# Front_panel_piezo.net
KiCad netlist of a schematic drawn in EAGLE
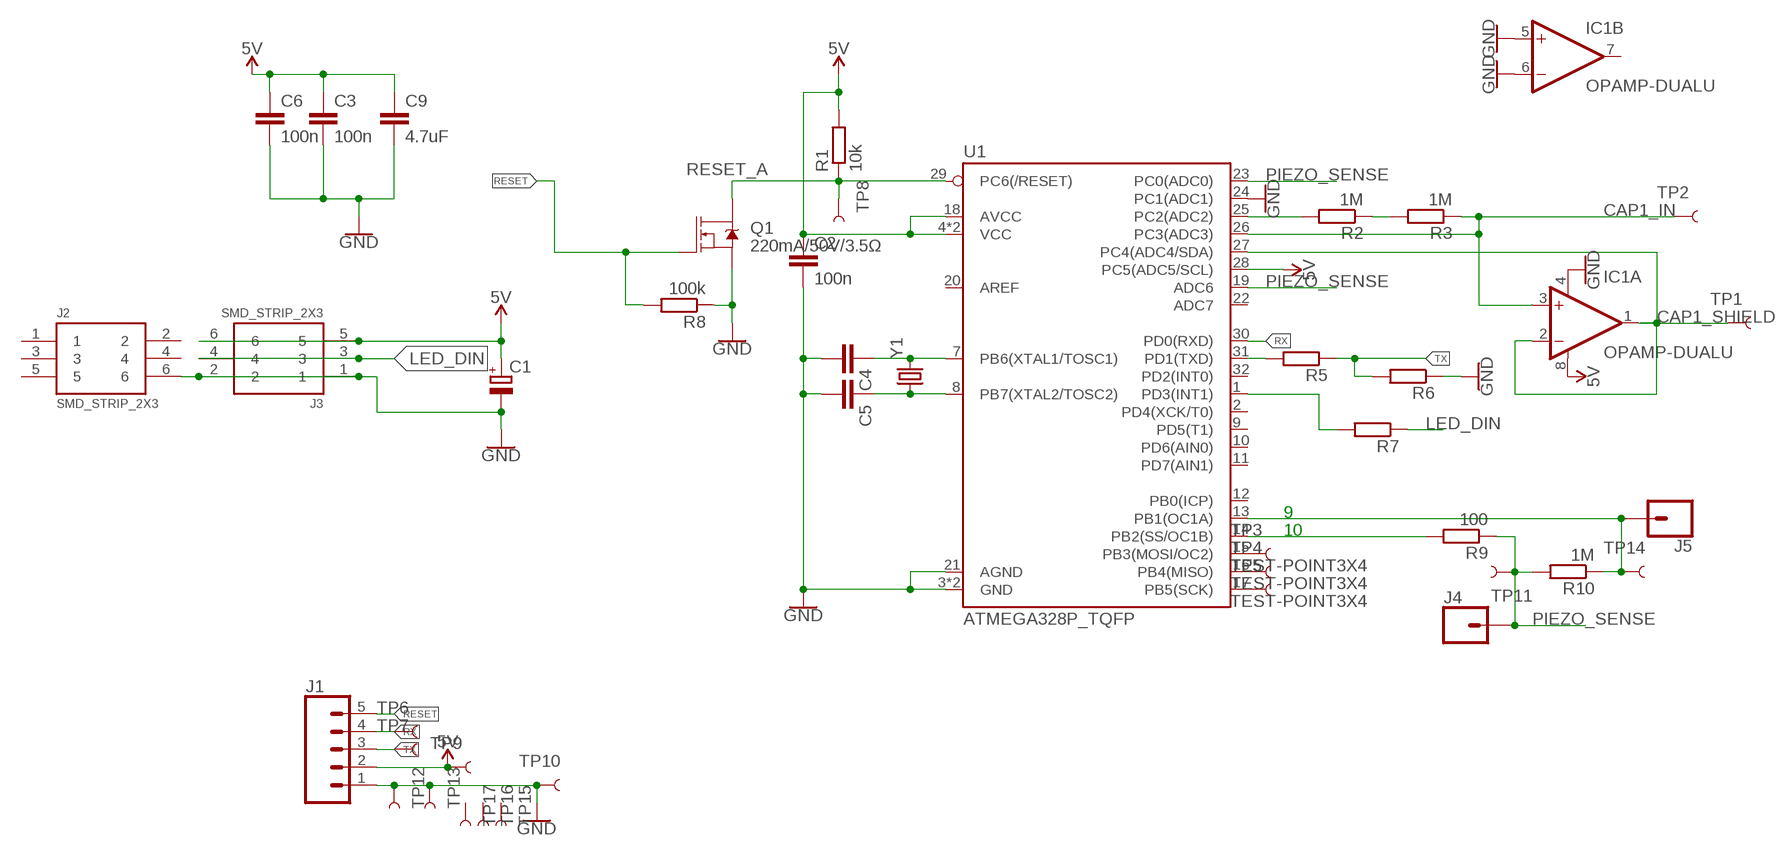
[diagram p0: schematic, sheet 1]

(export (version "E")
  (design (tool "Eeschema 10.0.6"))
  (components
    (comp (ref "C1")
      (value "CPOL-EUCT6032")
      (footprint "eagle-import:CT6032")
      (libsource (lib "eagle-import") (part "CPOL-EUCT6032"))
    )
    (comp (ref "C2")
      (value "100n")
      (footprint "eagle-import:C0805")
      (libsource (lib "eagle-import") (part "C-EUC0805"))
    )
    (comp (ref "C3")
      (value "100n")
      (footprint "eagle-import:C0805")
      (libsource (lib "eagle-import") (part "C-EUC0805"))
    )
    (comp (ref "C4")
      (value "C-EUC0805")
      (footprint "eagle-import:C0805")
      (libsource (lib "eagle-import") (part "C-EUC0805"))
    )
    (comp (ref "C5")
      (value "C-EUC0805")
      (footprint "eagle-import:C0805")
      (libsource (lib "eagle-import") (part "C-EUC0805"))
    )
    (comp (ref "C6")
      (value "100n")
      (footprint "eagle-import:C0805")
      (libsource (lib "eagle-import") (part "C-EUC0805"))
    )
    (comp (ref "C9")
      (value "4.7uF")
      (footprint "eagle-import:C0805")
      (libsource (lib "eagle-import") (part "C-EUC0805"))
    )
    (comp (ref "IC1")
      (value "OPAMP-DUALU")
      (footprint "eagle-import:SO08")
      (libsource (lib "eagle-import") (part "OPAMP-DUALU"))
    )
    (comp (ref "J1")
      (value "CONN_05SMD2")
      (footprint "eagle-import:1X05_1MM_RA")
      (libsource (lib "eagle-import") (part "CONN_05SMD2"))
    )
    (comp (ref "J2")
      (value "SMD_STRIP_2X3")
      (footprint "eagle-import:SMD_STRIP_2X3")
      (libsource (lib "eagle-import") (part "SMD_STRIP_2X3"))
    )
    (comp (ref "J3")
      (value "SMD_STRIP_2X3")
      (footprint "eagle-import:SMD_STRIP_2X3")
      (libsource (lib "eagle-import") (part "SMD_STRIP_2X3"))
    )
    (comp (ref "J4")
      (value "CONN_01SPRING-CONN")
      (footprint "eagle-import:SPRING-CONNECTOR")
      (libsource (lib "eagle-import") (part "CONN_01SPRING-CONN"))
    )
    (comp (ref "J5")
      (value "CONN_01SPRING-CONN")
      (footprint "eagle-import:SPRING-CONNECTOR")
      (libsource (lib "eagle-import") (part "CONN_01SPRING-CONN"))
    )
    (comp (ref "Q1")
      (value "220mA/50V/3.5Ω")
      (footprint "eagle-import:SOT23-3")
      (libsource (lib "eagle-import") (part "MOSFET-NCH-BSS138"))
    )
    (comp (ref "R1")
      (value "10k")
      (footprint "eagle-import:R0805")
      (libsource (lib "eagle-import") (part "R-EU_R0805"))
    )
    (comp (ref "R2")
      (value "1M")
      (footprint "eagle-import:R0805")
      (libsource (lib "eagle-import") (part "R-EU_R0805"))
    )
    (comp (ref "R3")
      (value "1M")
      (footprint "eagle-import:R0805")
      (libsource (lib "eagle-import") (part "R-EU_R0805"))
    )
    (comp (ref "R5")
      (value "R-EU_R0805")
      (footprint "eagle-import:R0805")
      (libsource (lib "eagle-import") (part "R-EU_R0805"))
    )
    (comp (ref "R6")
      (value "R-EU_R0805")
      (footprint "eagle-import:R0805")
      (libsource (lib "eagle-import") (part "R-EU_R0805"))
    )
    (comp (ref "R7")
      (value "R-EU_R0805")
      (footprint "eagle-import:R0805")
      (libsource (lib "eagle-import") (part "R-EU_R0805"))
    )
    (comp (ref "R8")
      (value "100k")
      (footprint "eagle-import:R0805")
      (libsource (lib "eagle-import") (part "R-EU_R0805"))
    )
    (comp (ref "R9")
      (value "100")
      (footprint "eagle-import:R0805")
      (libsource (lib "eagle-import") (part "R-EU_R0805"))
    )
    (comp (ref "R10")
      (value "1M")
      (footprint "eagle-import:R0805")
      (libsource (lib "eagle-import") (part "R-EU_R0805"))
    )
    (comp (ref "TP1")
      (value "TEST-POINT3X4")
      (footprint "eagle-import:PAD.03X.04")
      (libsource (lib "eagle-import") (part "TEST-POINT3X4"))
    )
    (comp (ref "TP2")
      (value "TEST-POINT3X4")
      (footprint "eagle-import:PAD.03X.04")
      (libsource (lib "eagle-import") (part "TEST-POINT3X4"))
    )
    (comp (ref "TP3")
      (value "TEST-POINT3X4")
      (footprint "eagle-import:PAD.03X.04")
      (libsource (lib "eagle-import") (part "TEST-POINT3X4"))
    )
    (comp (ref "TP4")
      (value "TEST-POINT3X4")
      (footprint "eagle-import:PAD.03X.04")
      (libsource (lib "eagle-import") (part "TEST-POINT3X4"))
    )
    (comp (ref "TP5")
      (value "TEST-POINT3X4")
      (footprint "eagle-import:PAD.03X.04")
      (libsource (lib "eagle-import") (part "TEST-POINT3X4"))
    )
    (comp (ref "TP6")
      (value "TEST-POINT3X4")
      (footprint "eagle-import:PAD.03X.04")
      (libsource (lib "eagle-import") (part "TEST-POINT3X4"))
    )
    (comp (ref "TP7")
      (value "TEST-POINT3X4")
      (footprint "eagle-import:PAD.03X.04")
      (libsource (lib "eagle-import") (part "TEST-POINT3X4"))
    )
    (comp (ref "TP8")
      (value "TEST-POINT3X4")
      (footprint "eagle-import:PAD.03X.04")
      (libsource (lib "eagle-import") (part "TEST-POINT3X4"))
    )
    (comp (ref "TP9")
      (value "TEST-POINT3X4")
      (footprint "eagle-import:PAD.03X.04")
      (libsource (lib "eagle-import") (part "TEST-POINT3X4"))
    )
    (comp (ref "TP10")
      (value "TEST-POINT3X4")
      (footprint "eagle-import:PAD.03X.04")
      (libsource (lib "eagle-import") (part "TEST-POINT3X4"))
    )
    (comp (ref "TP11")
      (value "TEST-POINT3X4")
      (footprint "eagle-import:PAD.03X.04")
      (libsource (lib "eagle-import") (part "TEST-POINT3X4"))
    )
    (comp (ref "TP12")
      (value "TEST-POINT3X4")
      (footprint "eagle-import:PAD.03X.04")
      (libsource (lib "eagle-import") (part "TEST-POINT3X4"))
    )
    (comp (ref "TP13")
      (value "TEST-POINT3X4")
      (footprint "eagle-import:PAD.03X.04")
      (libsource (lib "eagle-import") (part "TEST-POINT3X4"))
    )
    (comp (ref "TP14")
      (value "TEST-POINT3X4")
      (footprint "eagle-import:PAD.03X.04")
      (libsource (lib "eagle-import") (part "TEST-POINT3X4"))
    )
    (comp (ref "TP15")
      (value "TEST-POINT3X4")
      (footprint "eagle-import:PAD.03X.04")
      (libsource (lib "eagle-import") (part "TEST-POINT3X4"))
    )
    (comp (ref "TP16")
      (value "TEST-POINT3X4")
      (footprint "eagle-import:PAD.03X.04")
      (libsource (lib "eagle-import") (part "TEST-POINT3X4"))
    )
    (comp (ref "TP17")
      (value "TEST-POINT3X4")
      (footprint "eagle-import:PAD.03X.04")
      (libsource (lib "eagle-import") (part "TEST-POINT3X4"))
    )
    (comp (ref "U1")
      (value "ATMEGA328P_TQFP")
      (footprint "eagle-import:TQFP32-08")
      (libsource (lib "eagle-import") (part "ATMEGA328P_TQFP"))
    )
    (comp (ref "Y1")
      (value "CRYSTALSMD-3.2X2.5")
      (footprint "eagle-import:CRYSTAL-SMD-3.2X2.5MM")
      (libsource (lib "eagle-import") (part "CRYSTALSMD-3.2X2.5"))
    )
  )
  (nets
    (net (code "1") (name "/CAP1_IN") (class "Default")
      (node (ref "IC1") (pin "3") (pinfunction "+IN_3") (pintype "input"))
      (node (ref "R3") (pin "1") (pinfunction "1_1") (pintype "passive"))
      (node (ref "TP2") (pin "P$1") (pinfunction "1_P$1") (pintype "bidirectional"))
      (node (ref "U1") (pin "26") (pinfunction "PC3(ADC3)_26") (pintype "bidirectional"))
    )
    (net (code "2") (name "/CAP1_SHIELD") (class "Default")
      (node (ref "IC1") (pin "1") (pinfunction "OUT_1") (pintype "output"))
      (node (ref "IC1") (pin "2") (pinfunction "-IN_2") (pintype "input"))
      (node (ref "TP1") (pin "P$1") (pinfunction "1_P$1") (pintype "bidirectional"))
      (node (ref "U1") (pin "27") (pinfunction "PC4(ADC4/SDA)_27") (pintype "bidirectional"))
    )
    (net (code "3") (name "/PIEZO_SENSE") (class "Default")
      (node (ref "J4") (pin "P$2") (pinfunction "1_P$2") (pintype "passive"))
      (node (ref "R10") (pin "2") (pinfunction "2_2") (pintype "passive"))
      (node (ref "R9") (pin "1") (pinfunction "1_1") (pintype "passive"))
      (node (ref "TP11") (pin "P$1") (pinfunction "1_P$1") (pintype "bidirectional"))
      (node (ref "U1") (pin "19") (pinfunction "ADC6_19") (pintype "bidirectional"))
      (node (ref "U1") (pin "23") (pinfunction "PC0(ADC0)_23") (pintype "bidirectional"))
    )
    (net (code "4") (name "/RESET_A") (class "Default")
      (node (ref "Q1") (pin "3") (pinfunction "D_3") (pintype "bidirectional"))
      (node (ref "R1") (pin "1") (pinfunction "1_1") (pintype "passive"))
      (node (ref "TP8") (pin "P$1") (pinfunction "1_P$1") (pintype "bidirectional"))
      (node (ref "U1") (pin "29") (pinfunction "PC6(/RESET)_29") (pintype "bidirectional"))
    )
    (net (code "5") (name "5V") (class "Default")
      (node (ref "C1") (pin "-") (pinfunction "+_-") (pintype "passive"))
      (node (ref "C2") (pin "1") (pinfunction "1_1") (pintype "passive"))
      (node (ref "C3") (pin "1") (pinfunction "1_1") (pintype "passive"))
      (node (ref "C6") (pin "1") (pinfunction "1_1") (pintype "passive"))
      (node (ref "C9") (pin "1") (pinfunction "1_1") (pintype "passive"))
      (node (ref "IC1") (pin "8") (pinfunction "V+_8") (pintype "power_in"))
      (node (ref "J1") (pin "2") (pinfunction "2_2") (pintype "passive"))
      (node (ref "J3") (pin "5") (pinfunction "5_5") (pintype "bidirectional"))
      (node (ref "J3") (pin "6") (pinfunction "6_6") (pintype "bidirectional"))
      (node (ref "R1") (pin "2") (pinfunction "2_2") (pintype "passive"))
      (node (ref "TP9") (pin "P$1") (pinfunction "1_P$1") (pintype "bidirectional"))
      (node (ref "U1") (pin "18") (pinfunction "AVCC_18") (pintype "bidirectional"))
      (node (ref "U1") (pin "28") (pinfunction "PC5(ADC5/SCL)_28") (pintype "bidirectional"))
      (node (ref "U1") (pin "4") (pinfunction "VCC_4") (pintype "bidirectional"))
      (node (ref "U1") (pin "6") (pinfunction "VCC_6") (pintype "bidirectional"))
    )
    (net (code "6") (name "GND") (class "Default")
      (node (ref "C1") (pin "+") (pinfunction "-_+") (pintype "passive"))
      (node (ref "C2") (pin "2") (pinfunction "2_2") (pintype "passive"))
      (node (ref "C3") (pin "2") (pinfunction "2_2") (pintype "passive"))
      (node (ref "C4") (pin "2") (pinfunction "2_2") (pintype "passive"))
      (node (ref "C5") (pin "2") (pinfunction "2_2") (pintype "passive"))
      (node (ref "C6") (pin "2") (pinfunction "2_2") (pintype "passive"))
      (node (ref "C9") (pin "2") (pinfunction "2_2") (pintype "passive"))
      (node (ref "IC1") (pin "4") (pinfunction "V-_4") (pintype "power_in"))
      (node (ref "IC1") (pin "5") (pinfunction "+IN_5") (pintype "input"))
      (node (ref "IC1") (pin "6") (pinfunction "-IN_6") (pintype "input"))
      (node (ref "J1") (pin "1") (pinfunction "1_1") (pintype "passive"))
      (node (ref "J2") (pin "6") (pinfunction "6_6") (pintype "bidirectional"))
      (node (ref "J3") (pin "1") (pinfunction "1_1") (pintype "bidirectional"))
      (node (ref "J3") (pin "2") (pinfunction "2_2") (pintype "bidirectional"))
      (node (ref "Q1") (pin "2") (pinfunction "S_2") (pintype "bidirectional"))
      (node (ref "R6") (pin "1") (pinfunction "1_1") (pintype "passive"))
      (node (ref "R8") (pin "1") (pinfunction "1_1") (pintype "passive"))
      (node (ref "TP10") (pin "P$1") (pinfunction "1_P$1") (pintype "bidirectional"))
      (node (ref "TP12") (pin "P$1") (pinfunction "1_P$1") (pintype "bidirectional"))
      (node (ref "TP13") (pin "P$1") (pinfunction "1_P$1") (pintype "bidirectional"))
      (node (ref "U1") (pin "21") (pinfunction "AGND_21") (pintype "bidirectional"))
      (node (ref "U1") (pin "24") (pinfunction "PC1(ADC1)_24") (pintype "bidirectional"))
      (node (ref "U1") (pin "3") (pinfunction "GND_3") (pintype "bidirectional"))
      (node (ref "U1") (pin "5") (pinfunction "GND_5") (pintype "bidirectional"))
    )
    (net (code "7") (name "LED_DIN") (class "Default")
      (node (ref "J3") (pin "3") (pinfunction "3_3") (pintype "bidirectional"))
      (node (ref "J3") (pin "4") (pinfunction "4_4") (pintype "bidirectional"))
      (node (ref "R7") (pin "1") (pinfunction "1_1") (pintype "passive"))
    )
    (net (code "8") (name "Net-(J5-1)") (class "Default")
      (node (ref "J5") (pin "P$2") (pinfunction "1_P$2") (pintype "passive"))
      (node (ref "R10") (pin "1") (pinfunction "1_1") (pintype "passive"))
      (node (ref "TP14") (pin "P$1") (pinfunction "1_P$1") (pintype "bidirectional"))
      (node (ref "U1") (pin "13") (pinfunction "PB1(OC1A)_13") (pintype "bidirectional"))
    )
    (net (code "9") (name "Net-(R2-Pad1)") (class "Default")
      (node (ref "R2") (pin "1") (pinfunction "1_1") (pintype "passive"))
      (node (ref "R3") (pin "2") (pinfunction "2_2") (pintype "passive"))
    )
    (net (code "10") (name "Net-(TP3-1)") (class "Default")
      (node (ref "TP3") (pin "P$1") (pinfunction "1_P$1") (pintype "bidirectional"))
      (node (ref "U1") (pin "15") (pinfunction "PB3(MOSI/OC2)_15") (pintype "bidirectional"))
    )
    (net (code "11") (name "Net-(TP4-1)") (class "Default")
      (node (ref "TP4") (pin "P$1") (pinfunction "1_P$1") (pintype "bidirectional"))
      (node (ref "U1") (pin "16") (pinfunction "PB4(MISO)_16") (pintype "bidirectional"))
    )
    (net (code "12") (name "Net-(TP5-1)") (class "Default")
      (node (ref "TP5") (pin "P$1") (pinfunction "1_P$1") (pintype "bidirectional"))
      (node (ref "U1") (pin "17") (pinfunction "PB5(SCK)_17") (pintype "bidirectional"))
    )
    (net (code "13") (name "Net-(U1-PB2(SS{slash}OC1B))") (class "Default")
      (node (ref "R9") (pin "2") (pinfunction "2_2") (pintype "passive"))
      (node (ref "U1") (pin "14") (pinfunction "PB2(SS/OC1B)_14") (pintype "bidirectional"))
    )
    (net (code "14") (name "Net-(U1-PB6(XTAL1{slash}TOSC1))") (class "Default")
      (node (ref "C4") (pin "1") (pinfunction "1_1") (pintype "passive"))
      (node (ref "U1") (pin "7") (pinfunction "PB6(XTAL1/TOSC1)_7") (pintype "bidirectional"))
      (node (ref "Y1") (pin "3") (pinfunction "2_3") (pintype "passive"))
    )
    (net (code "15") (name "Net-(U1-PB7(XTAL2{slash}TOSC2))") (class "Default")
      (node (ref "C5") (pin "1") (pinfunction "1_1") (pintype "passive"))
      (node (ref "U1") (pin "8") (pinfunction "PB7(XTAL2/TOSC2)_8") (pintype "bidirectional"))
      (node (ref "Y1") (pin "1") (pinfunction "1_1") (pintype "passive"))
    )
    (net (code "16") (name "Net-(U1-PC2(ADC2))") (class "Default")
      (node (ref "R2") (pin "2") (pinfunction "2_2") (pintype "passive"))
      (node (ref "U1") (pin "25") (pinfunction "PC2(ADC2)_25") (pintype "bidirectional"))
    )
    (net (code "17") (name "Net-(U1-PD1(TXD))") (class "Default")
      (node (ref "R5") (pin "2") (pinfunction "2_2") (pintype "passive"))
      (node (ref "U1") (pin "31") (pinfunction "PD1(TXD)_31") (pintype "bidirectional"))
    )
    (net (code "18") (name "Net-(U1-PD3(INT1))") (class "Default")
      (node (ref "R7") (pin "2") (pinfunction "2_2") (pintype "passive"))
      (node (ref "U1") (pin "1") (pinfunction "PD3(INT1)_1") (pintype "bidirectional"))
    )
    (net (code "19") (name "RESET") (class "Default")
      (node (ref "J1") (pin "5") (pinfunction "5_5") (pintype "passive"))
      (node (ref "Q1") (pin "1") (pinfunction "G_1") (pintype "bidirectional"))
      (node (ref "R8") (pin "2") (pinfunction "2_2") (pintype "passive"))
    )
    (net (code "20") (name "RX") (class "Default")
      (node (ref "J1") (pin "4") (pinfunction "4_4") (pintype "passive"))
      (node (ref "TP6") (pin "P$1") (pinfunction "1_P$1") (pintype "bidirectional"))
      (node (ref "U1") (pin "30") (pinfunction "PD0(RXD)_30") (pintype "bidirectional"))
    )
    (net (code "21") (name "TX") (class "Default")
      (node (ref "J1") (pin "3") (pinfunction "3_3") (pintype "passive"))
      (node (ref "R5") (pin "1") (pinfunction "1_1") (pintype "passive"))
      (node (ref "R6") (pin "2") (pinfunction "2_2") (pintype "passive"))
      (node (ref "TP7") (pin "P$1") (pinfunction "1_P$1") (pintype "bidirectional"))
    )
    (net (code "22") (name "unconnected-(IC1B-OUT-Pad7)") (class "Default")
      (node (ref "IC1") (pin "7") (pinfunction "OUT_7") (pintype "output"))
    )
    (net (code "23") (name "unconnected-(J2-Pad1)") (class "Default")
      (node (ref "J2") (pin "1") (pinfunction "1_1") (pintype "bidirectional"))
    )
    (net (code "24") (name "unconnected-(J2-Pad2)") (class "Default")
      (node (ref "J2") (pin "2") (pinfunction "2_2") (pintype "bidirectional"))
    )
    (net (code "25") (name "unconnected-(J2-Pad3)") (class "Default")
      (node (ref "J2") (pin "3") (pinfunction "3_3") (pintype "bidirectional"))
    )
    (net (code "26") (name "unconnected-(J2-Pad4)") (class "Default")
      (node (ref "J2") (pin "4") (pinfunction "4_4") (pintype "bidirectional"))
    )
    (net (code "27") (name "unconnected-(J2-Pad5)") (class "Default")
      (node (ref "J2") (pin "5") (pinfunction "5_5") (pintype "bidirectional"))
    )
    (net (code "28") (name "unconnected-(TP15-1-PadP$1)") (class "Default")
      (node (ref "TP15") (pin "P$1") (pinfunction "1_P$1") (pintype "bidirectional"))
    )
    (net (code "29") (name "unconnected-(TP16-1-PadP$1)") (class "Default")
      (node (ref "TP16") (pin "P$1") (pinfunction "1_P$1") (pintype "bidirectional"))
    )
    (net (code "30") (name "unconnected-(TP17-1-PadP$1)") (class "Default")
      (node (ref "TP17") (pin "P$1") (pinfunction "1_P$1") (pintype "bidirectional"))
    )
    (net (code "31") (name "unconnected-(U1-ADC7-Pad22)") (class "Default")
      (node (ref "U1") (pin "22") (pinfunction "ADC7_22") (pintype "bidirectional"))
    )
    (net (code "32") (name "unconnected-(U1-AREF-Pad20)") (class "Default")
      (node (ref "U1") (pin "20") (pinfunction "AREF_20") (pintype "bidirectional"))
    )
    (net (code "33") (name "unconnected-(U1-PB0(ICP)-Pad12)") (class "Default")
      (node (ref "U1") (pin "12") (pinfunction "PB0(ICP)_12") (pintype "bidirectional"))
    )
    (net (code "34") (name "unconnected-(U1-PD2(INT0)-Pad32)") (class "Default")
      (node (ref "U1") (pin "32") (pinfunction "PD2(INT0)_32") (pintype "bidirectional"))
    )
    (net (code "35") (name "unconnected-(U1-PD4(XCK{slash}T0)-Pad2)") (class "Default")
      (node (ref "U1") (pin "2") (pinfunction "PD4(XCK/T0)_2") (pintype "bidirectional"))
    )
    (net (code "36") (name "unconnected-(U1-PD5(T1)-Pad9)") (class "Default")
      (node (ref "U1") (pin "9") (pinfunction "PD5(T1)_9") (pintype "bidirectional"))
    )
    (net (code "37") (name "unconnected-(U1-PD6(AIN0)-Pad10)") (class "Default")
      (node (ref "U1") (pin "10") (pinfunction "PD6(AIN0)_10") (pintype "bidirectional"))
    )
    (net (code "38") (name "unconnected-(U1-PD7(AIN1)-Pad11)") (class "Default")
      (node (ref "U1") (pin "11") (pinfunction "PD7(AIN1)_11") (pintype "bidirectional"))
    )
  )
)
